# BusPirate-v5.net
KiCad netlist of a schematic drawn in EAGLE
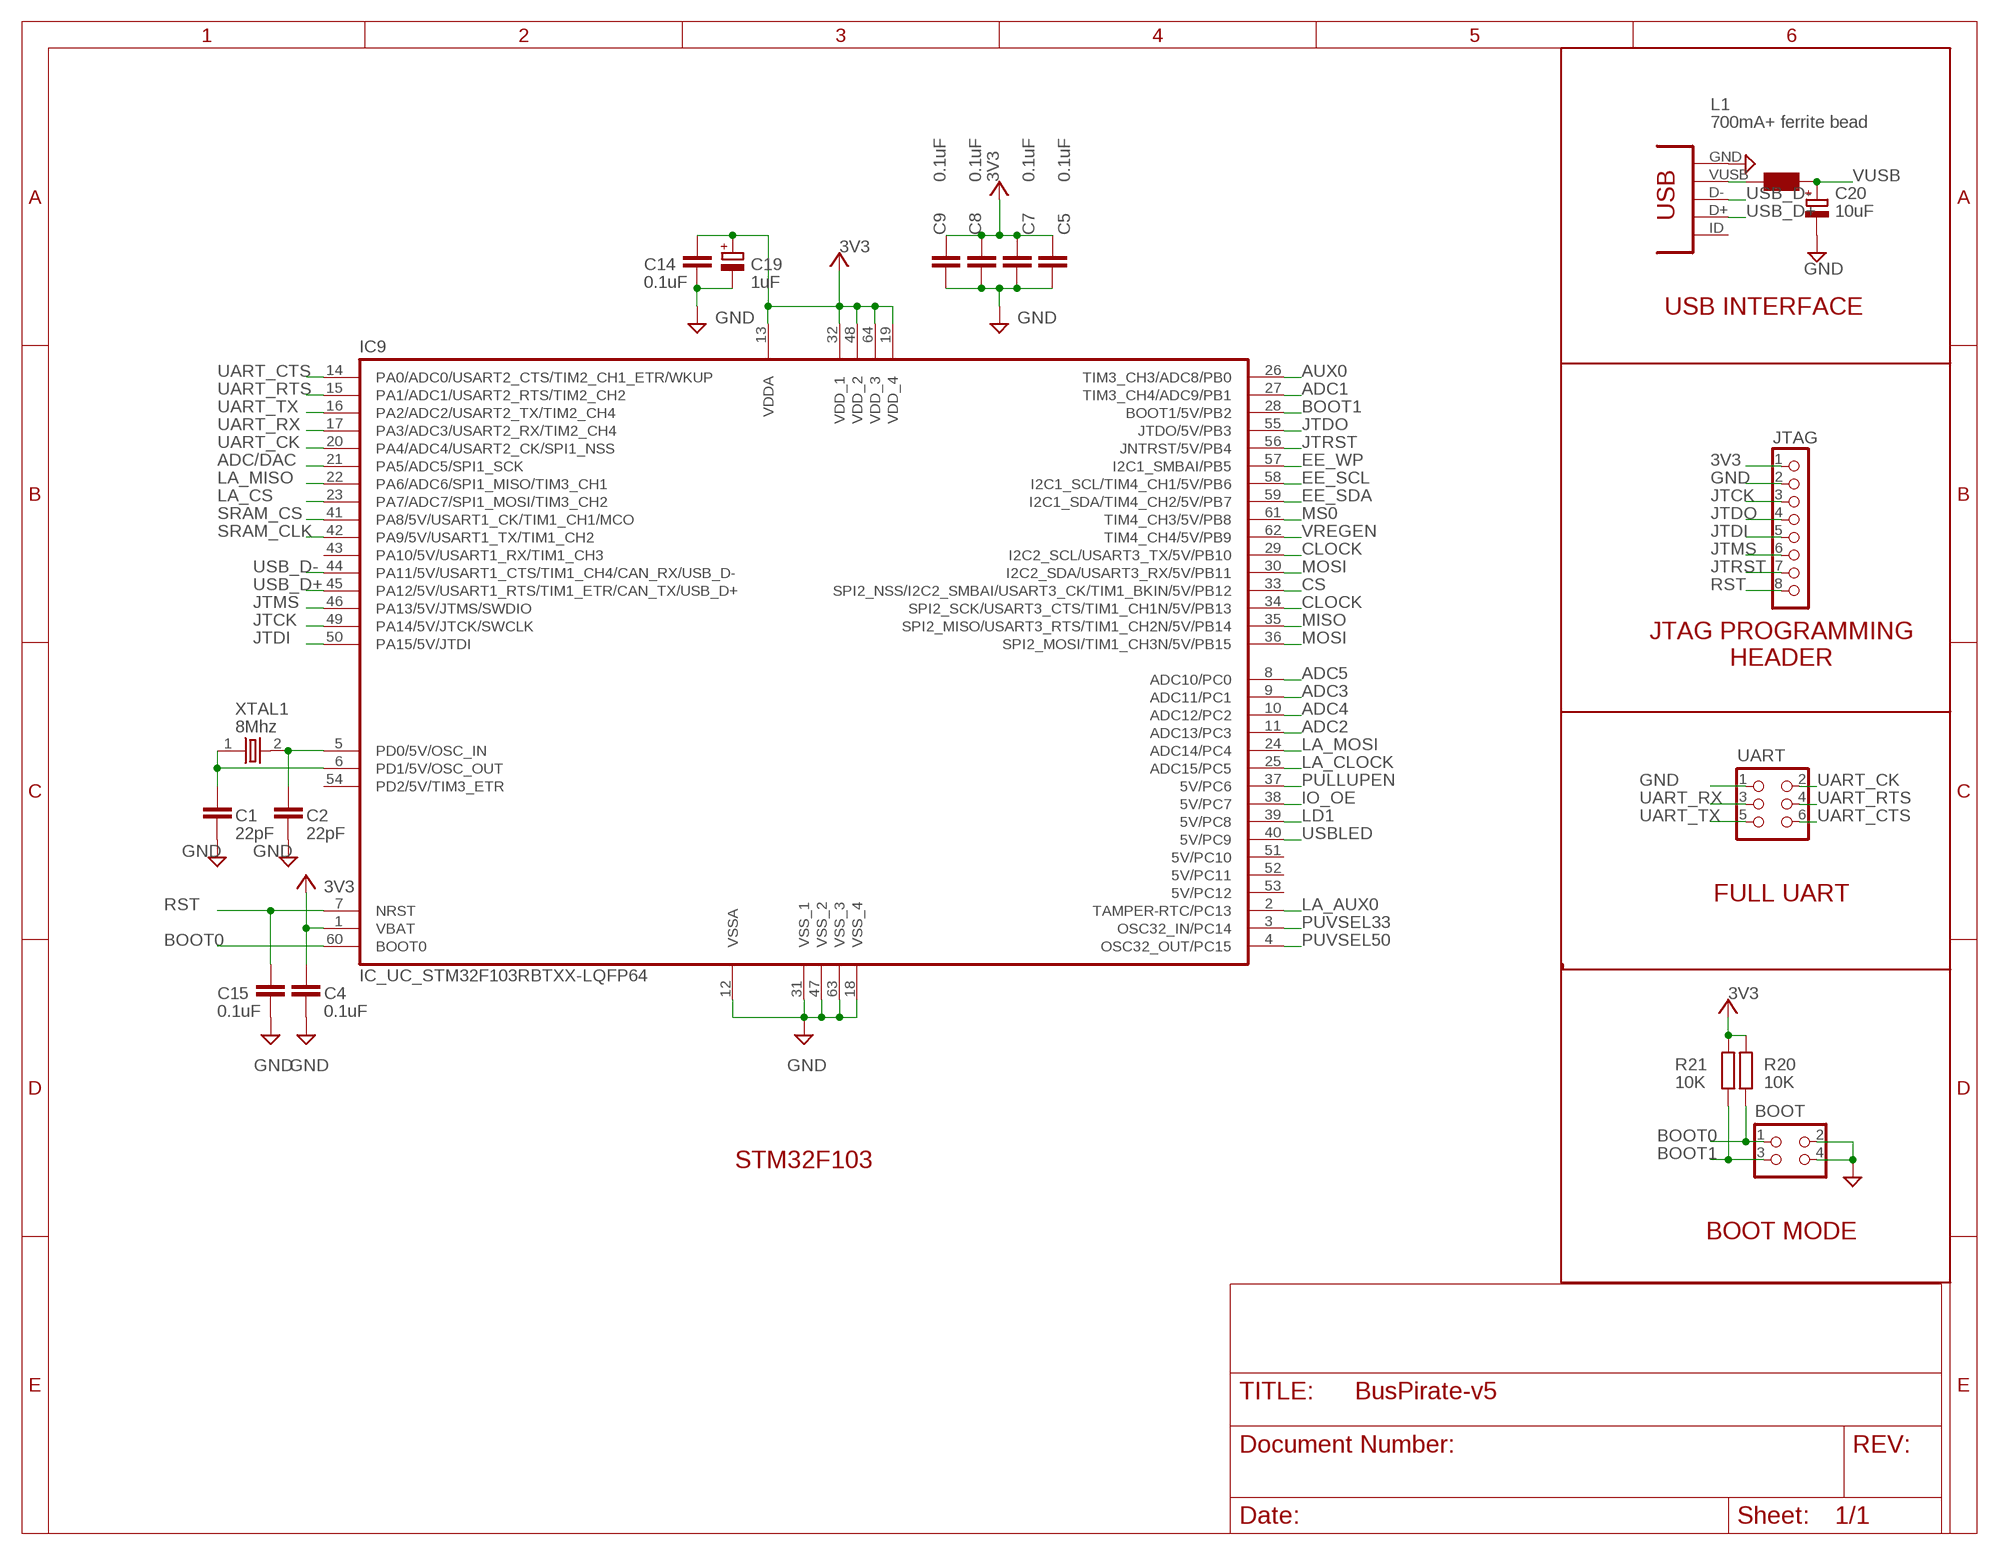
[diagram p0: schematic, sheet 1, part 1 of 2]
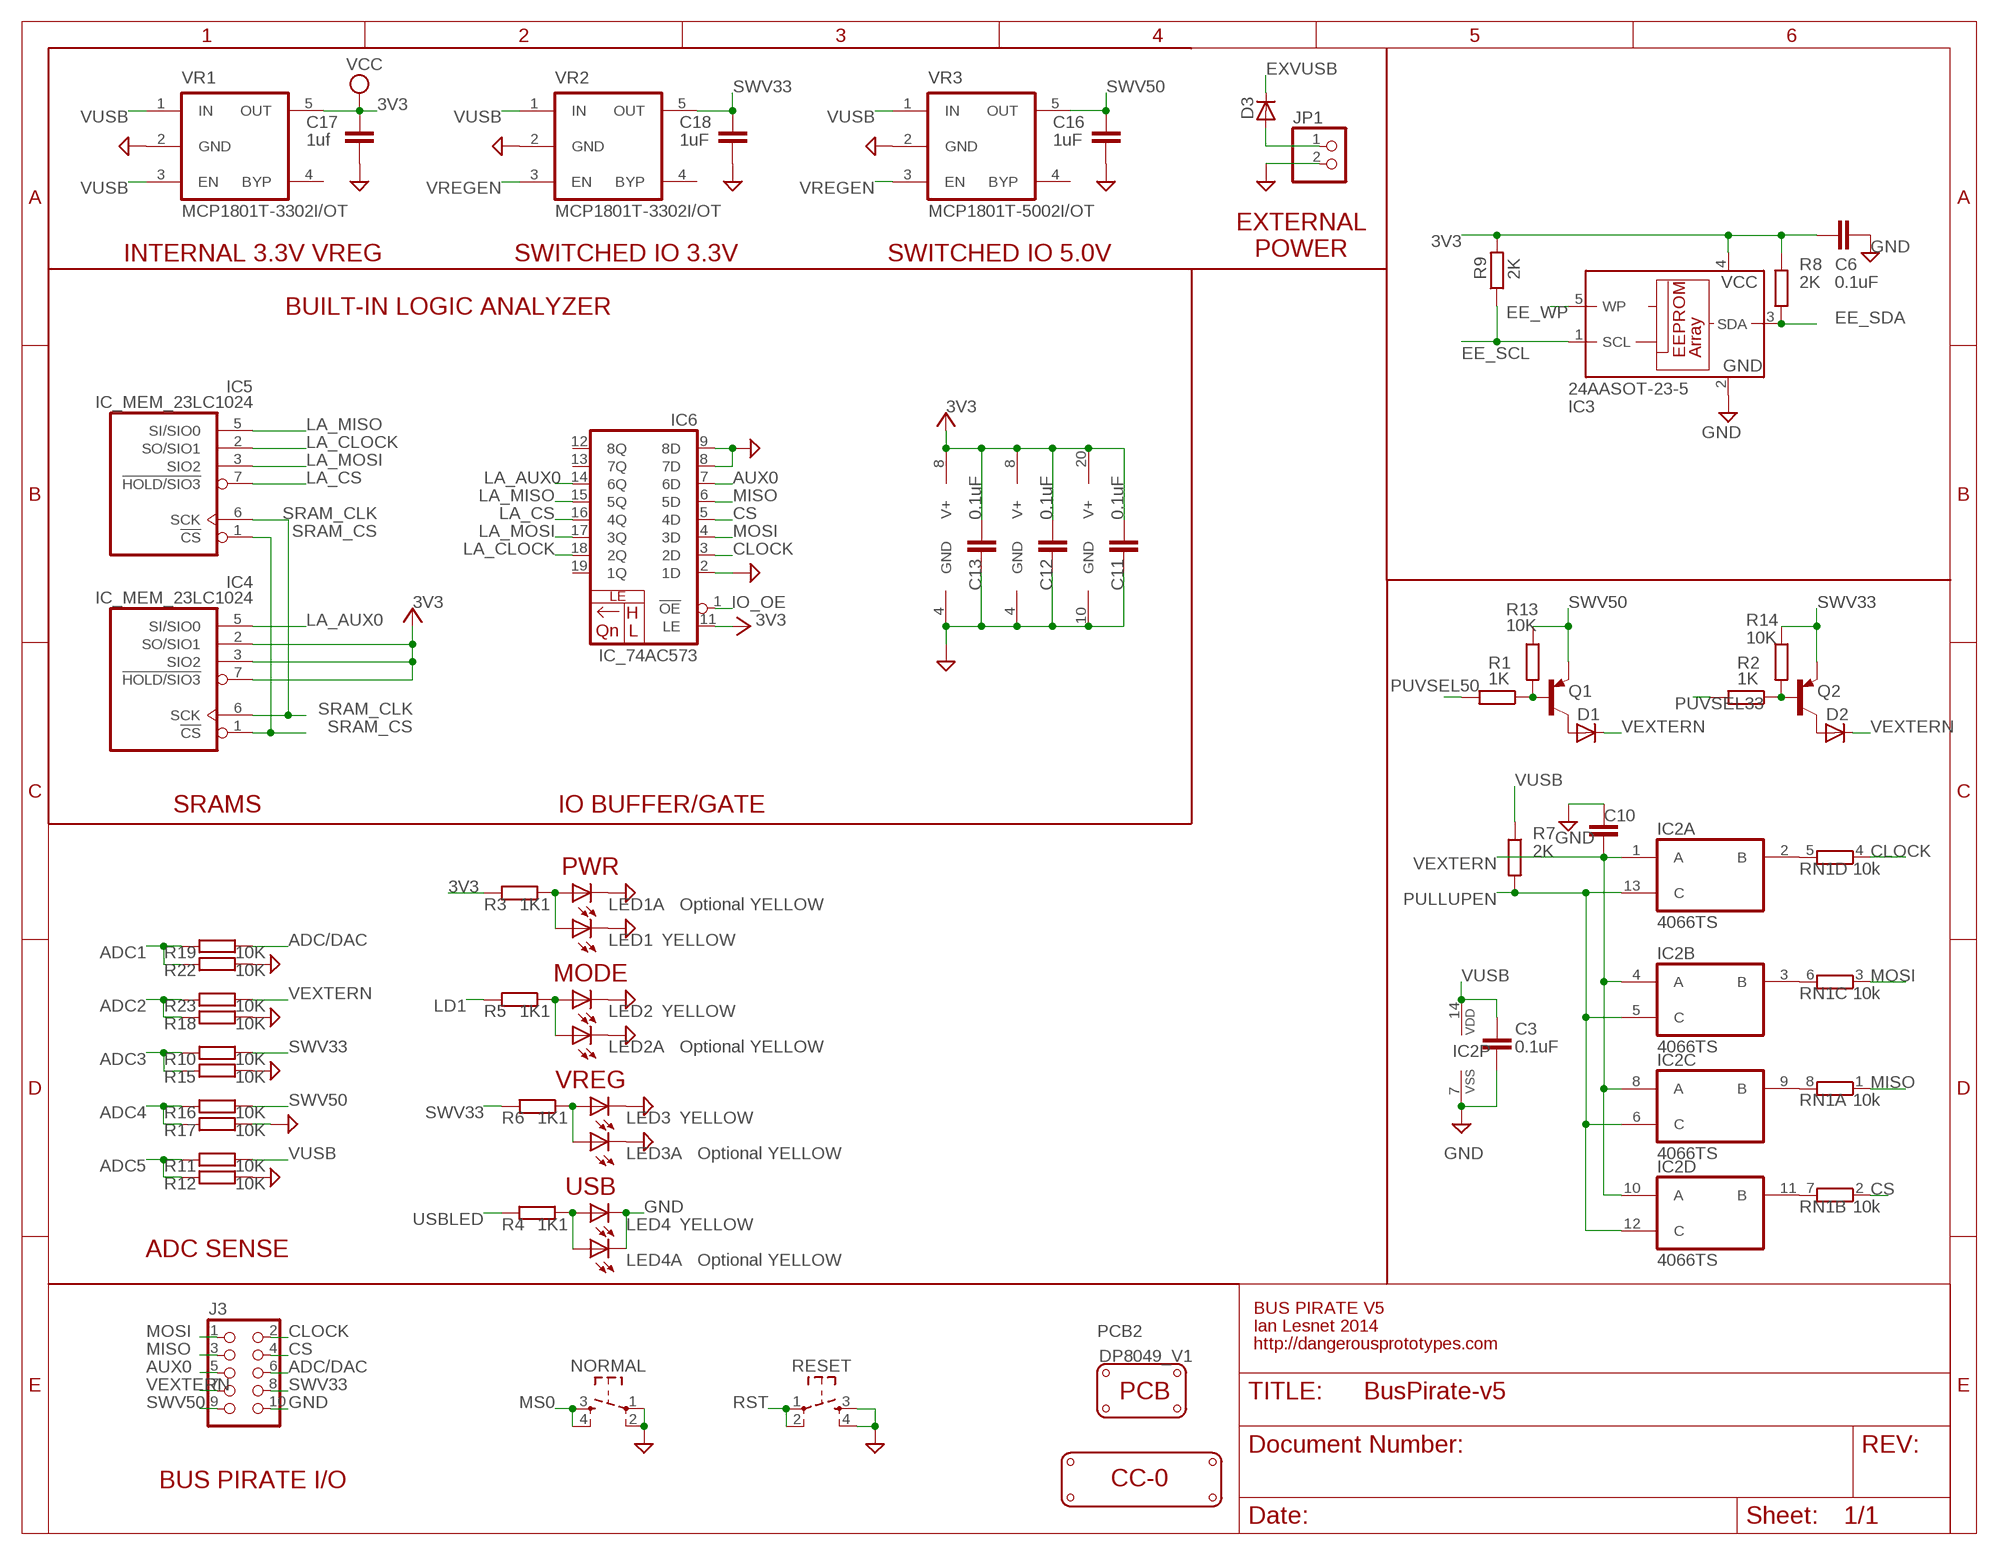
[diagram p1: schematic, sheet 1, part 2 of 2]

(export (version "E")
  (design (tool "Eeschema 10.0.6"))
  (components
    (comp (ref "BOOT")
      (value "CON_HEADER_2X02-PTH")
      (footprint "eagle-import:M2X2")
      (libsource (lib "eagle-import") (part "CON_HEADER_2X02-PTH"))
    )
    (comp (ref "C1")
      (value "22pF")
      (footprint "eagle-import:C0603")
      (libsource (lib "eagle-import") (part "C-EUC0603"))
    )
    (comp (ref "C2")
      (value "22pF")
      (footprint "eagle-import:C0603")
      (libsource (lib "eagle-import") (part "C-EUC0603"))
    )
    (comp (ref "C3")
      (value "0.1uF")
      (footprint "eagle-import:C0603")
      (libsource (lib "eagle-import") (part "C-EUC0603"))
    )
    (comp (ref "C4")
      (value "0.1uF")
      (footprint "eagle-import:C0603")
      (libsource (lib "eagle-import") (part "C-EUC0603"))
    )
    (comp (ref "C5")
      (value "0.1uF")
      (footprint "eagle-import:C0603")
      (libsource (lib "eagle-import") (part "C-EUC0603"))
    )
    (comp (ref "C6")
      (value "0.1uF")
      (footprint "eagle-import:C0603")
      (libsource (lib "eagle-import") (part "C-EUC0603"))
    )
    (comp (ref "C7")
      (value "0.1uF")
      (footprint "eagle-import:C0603")
      (libsource (lib "eagle-import") (part "C-EUC0603"))
    )
    (comp (ref "C8")
      (value "0.1uF")
      (footprint "eagle-import:C0603")
      (libsource (lib "eagle-import") (part "C-EUC0603"))
    )
    (comp (ref "C9")
      (value "0.1uF")
      (footprint "eagle-import:C0603")
      (libsource (lib "eagle-import") (part "C-EUC0603"))
    )
    (comp (ref "C10")
      (value "0.1uF")
      (footprint "eagle-import:C0603")
      (libsource (lib "eagle-import") (part "C-EUC0603"))
    )
    (comp (ref "C11")
      (value "0.1uF")
      (footprint "eagle-import:C0603")
      (libsource (lib "eagle-import") (part "C-EUC0603"))
    )
    (comp (ref "C12")
      (value "0.1uF")
      (footprint "eagle-import:C0603")
      (libsource (lib "eagle-import") (part "C-EUC0603"))
    )
    (comp (ref "C13")
      (value "0.1uF")
      (footprint "eagle-import:C0603")
      (libsource (lib "eagle-import") (part "C-EUC0603"))
    )
    (comp (ref "C14")
      (value "0.1uF")
      (footprint "eagle-import:C0603")
      (libsource (lib "eagle-import") (part "C-EUC0603"))
    )
    (comp (ref "C15")
      (value "0.1uF")
      (footprint "eagle-import:C0603")
      (libsource (lib "eagle-import") (part "C-EUC0603"))
    )
    (comp (ref "C16")
      (value "1uF")
      (footprint "eagle-import:C0603")
      (libsource (lib "eagle-import") (part "C-EUC0603"))
    )
    (comp (ref "C17")
      (value "1uf")
      (footprint "eagle-import:C0603")
      (libsource (lib "eagle-import") (part "C-EUC0603"))
    )
    (comp (ref "C18")
      (value "1uF")
      (footprint "eagle-import:C0603")
      (libsource (lib "eagle-import") (part "C-EUC0603"))
    )
    (comp (ref "C19")
      (value "1uF")
      (footprint "eagle-import:SMC_A")
      (libsource (lib "eagle-import") (part "CPOL-EUSMCA"))
    )
    (comp (ref "C20")
      (value "10uF")
      (footprint "eagle-import:SMC_A")
      (libsource (lib "eagle-import") (part "CPOL-EUSMCA"))
    )
    (comp (ref "D1")
      (value "MBR0520LT")
      (footprint "eagle-import:SOD123")
      (libsource (lib "eagle-import") (part "MBR0520LT"))
    )
    (comp (ref "D2")
      (value "MBR0520LT")
      (footprint "eagle-import:SOD123")
      (libsource (lib "eagle-import") (part "MBR0520LT"))
    )
    (comp (ref "D3")
      (value "MBR0520LT")
      (footprint "eagle-import:SOD123")
      (libsource (lib "eagle-import") (part "MBR0520LT"))
    )
    (comp (ref "IC2")
      (value "4066TS")
      (footprint "eagle-import:40XX_TSSOP14")
      (libsource (lib "eagle-import") (part "4066TS"))
    )
    (comp (ref "IC3")
      (value "24AASOT-23-5")
      (footprint "eagle-import:SOT-23-5@1")
      (libsource (lib "eagle-import") (part "24AA"))
    )
    (comp (ref "IC4")
      (value "IC_MEM_23LC1024")
      (footprint "eagle-import:SOIC-8")
      (libsource (lib "eagle-import") (part "IC_MEM_23LC1024"))
    )
    (comp (ref "IC5")
      (value "IC_MEM_23LC1024")
      (footprint "eagle-import:SOIC-8")
      (libsource (lib "eagle-import") (part "IC_MEM_23LC1024"))
    )
    (comp (ref "IC6")
      (value "IC_74AC573")
      (footprint "eagle-import:TSSOP-20")
      (libsource (lib "eagle-import") (part "IC_74AC573-TSSOP-20"))
    )
    (comp (ref "IC9")
      (value "IC_UC_STM32F103RBTXX-LQFP64")
      (footprint "eagle-import:LQFP64")
      (libsource (lib "eagle-import") (part "IC_UC_STM32F103RBTXX-LQFP64"))
    )
    (comp (ref "J3")
      (value "CON_HEADER_2X05-PTH+SHROUDED_A")
      (footprint "eagle-import:PINSHRD_PTH_2X05")
      (libsource (lib "eagle-import") (part "CON_HEADER_2X05-PTH+SHROUDED_A"))
    )
    (comp (ref "JP1")
      (value "PINHD-1X02_2.54-S")
      (footprint "eagle-import:1X02-S")
      (libsource (lib "eagle-import") (part "PINHD-1X02_2.54-S"))
    )
    (comp (ref "JTAG")
      (value "CON_HEADER_1X08-PTH")
      (footprint "eagle-import:M1X8")
      (libsource (lib "eagle-import") (part "CON_HEADER_1X08-PTH"))
    )
    (comp (ref "L1")
      (value "700mA+ ferrite bead")
      (footprint "eagle-import:WE-KI_0805_B")
      (libsource (lib "eagle-import") (part "WE-KIL_0805"))
    )
    (comp (ref "LED1")
      (value "YELLOW")
      (footprint "eagle-import:LED-603")
      (libsource (lib "eagle-import") (part "LED-0603"))
    )
    (comp (ref "LED1A")
      (value "Optional YELLOW")
      (footprint "eagle-import:LED-603")
      (libsource (lib "eagle-import") (part "LED-0603"))
    )
    (comp (ref "LED2")
      (value "YELLOW")
      (footprint "eagle-import:LED-603")
      (libsource (lib "eagle-import") (part "LED-0603"))
    )
    (comp (ref "LED2A")
      (value "Optional YELLOW")
      (footprint "eagle-import:LED-603")
      (libsource (lib "eagle-import") (part "LED-0603"))
    )
    (comp (ref "LED3")
      (value "YELLOW")
      (footprint "eagle-import:LED-603")
      (libsource (lib "eagle-import") (part "LED-0603"))
    )
    (comp (ref "LED3A")
      (value "Optional YELLOW")
      (footprint "eagle-import:LED-603")
      (libsource (lib "eagle-import") (part "LED-0603"))
    )
    (comp (ref "LED4")
      (value "YELLOW")
      (footprint "eagle-import:LED-603")
      (libsource (lib "eagle-import") (part "LED-0603"))
    )
    (comp (ref "LED4A")
      (value "Optional YELLOW")
      (footprint "eagle-import:LED-603")
      (libsource (lib "eagle-import") (part "LED-0603"))
    )
    (comp (ref "LOGO1")
      (value "LOGO_CC-0")
      (footprint "eagle-import:LOGO_CC-0")
      (libsource (lib "eagle-import") (part "LOGO_CC-0"))
    )
    (comp (ref "NORMAL")
      (value "SW_TACT_4P")
      (footprint "eagle-import:SW_TACT_SMALL")
      (libsource (lib "eagle-import") (part "SW_TACT_4P"))
    )
    (comp (ref "PCB2")
      (value "PCB_DP_RECTANGLE-80X49")
      (footprint "eagle-import:DP8049_V1")
      (fields (field (name "PCB_SIZE") "DP8049_V1"))
      (libsource (lib "eagle-import") (part "PCB_DP_RECTANGLE-80X49"))
    )
    (comp (ref "Q1")
      (value "MMBTA56-SOT23")
      (footprint "eagle-import:SOT23")
      (libsource (lib "eagle-import") (part "-?SOT23MMBTA56"))
    )
    (comp (ref "Q2")
      (value "MMBTA56-SOT23")
      (footprint "eagle-import:SOT23")
      (libsource (lib "eagle-import") (part "-?SOT23MMBTA56"))
    )
    (comp (ref "R1")
      (value "1K")
      (footprint "eagle-import:R0603")
      (libsource (lib "eagle-import") (part "R-EU_R0603"))
    )
    (comp (ref "R2")
      (value "1K")
      (footprint "eagle-import:R0603")
      (libsource (lib "eagle-import") (part "R-EU_R0603"))
    )
    (comp (ref "R3")
      (value "1K1")
      (footprint "eagle-import:R603")
      (libsource (lib "eagle-import") (part "RESISTOR-0603"))
    )
    (comp (ref "R4")
      (value "1K1")
      (footprint "eagle-import:R603")
      (libsource (lib "eagle-import") (part "RESISTOR-0603"))
    )
    (comp (ref "R5")
      (value "1K1")
      (footprint "eagle-import:R603")
      (libsource (lib "eagle-import") (part "RESISTOR-0603"))
    )
    (comp (ref "R6")
      (value "1K1")
      (footprint "eagle-import:R603")
      (libsource (lib "eagle-import") (part "RESISTOR-0603"))
    )
    (comp (ref "R7")
      (value "2K")
      (footprint "eagle-import:R0603")
      (libsource (lib "eagle-import") (part "R-EU_R0603"))
    )
    (comp (ref "R8")
      (value "2K")
      (footprint "eagle-import:R0603")
      (libsource (lib "eagle-import") (part "R-EU_R0603"))
    )
    (comp (ref "R9")
      (value "2K")
      (footprint "eagle-import:R0603")
      (libsource (lib "eagle-import") (part "R-EU_R0603"))
    )
    (comp (ref "R10")
      (value "10K")
      (footprint "eagle-import:R0603")
      (libsource (lib "eagle-import") (part "resistor_R-EU_R0603"))
    )
    (comp (ref "R11")
      (value "10K")
      (footprint "eagle-import:R0603")
      (libsource (lib "eagle-import") (part "resistor_R-EU_R0603"))
    )
    (comp (ref "R12")
      (value "10K")
      (footprint "eagle-import:R0603")
      (libsource (lib "eagle-import") (part "resistor_R-EU_R0603"))
    )
    (comp (ref "R13")
      (value "10K")
      (footprint "eagle-import:R603")
      (libsource (lib "eagle-import") (part "RESISTOR-0603"))
    )
    (comp (ref "R14")
      (value "10K")
      (footprint "eagle-import:R0603")
      (libsource (lib "eagle-import") (part "R-EU_R0603"))
    )
    (comp (ref "R15")
      (value "10K")
      (footprint "eagle-import:R0603")
      (libsource (lib "eagle-import") (part "resistor_R-EU_R0603"))
    )
    (comp (ref "R16")
      (value "10K")
      (footprint "eagle-import:R0603")
      (libsource (lib "eagle-import") (part "resistor_R-EU_R0603"))
    )
    (comp (ref "R17")
      (value "10K")
      (footprint "eagle-import:R0603")
      (libsource (lib "eagle-import") (part "resistor_R-EU_R0603"))
    )
    (comp (ref "R18")
      (value "10K")
      (footprint "eagle-import:R0603")
      (libsource (lib "eagle-import") (part "resistor_R-EU_R0603"))
    )
    (comp (ref "R19")
      (value "10K")
      (footprint "eagle-import:R0603")
      (libsource (lib "eagle-import") (part "resistor_R-EU_R0603"))
    )
    (comp (ref "R20")
      (value "10K")
      (footprint "eagle-import:R0603")
      (libsource (lib "eagle-import") (part "R-EU_R0603"))
    )
    (comp (ref "R21")
      (value "10K")
      (footprint "eagle-import:R0603")
      (libsource (lib "eagle-import") (part "R-EU_R0603"))
    )
    (comp (ref "R22")
      (value "10K")
      (footprint "eagle-import:R0603")
      (libsource (lib "eagle-import") (part "resistor_R-EU_R0603"))
    )
    (comp (ref "R23")
      (value "10K")
      (footprint "eagle-import:R0603")
      (libsource (lib "eagle-import") (part "resistor_R-EU_R0603"))
    )
    (comp (ref "RESET")
      (value "SW_TACT_4P")
      (footprint "eagle-import:SW_TACT_SMALL")
      (libsource (lib "eagle-import") (part "SW_TACT_4P"))
    )
    (comp (ref "RN1")
      (value "10k")
      (footprint "eagle-import:RN8P-4R-CRA06S")
      (libsource (lib "eagle-import") (part "RNETWORK"))
    )
    (comp (ref "UART")
      (value "CON_HEADER_2X03-PTH")
      (footprint "eagle-import:M2X3")
      (libsource (lib "eagle-import") (part "CON_HEADER_2X03-PTH"))
    )
    (comp (ref "USB")
      (value "USB mini-b")
      (footprint "eagle-import:CONN_USB_MINI-B")
      (libsource (lib "eagle-import") (part "CON-USB-MINI-BUSB1"))
    )
    (comp (ref "VR1")
      (value "MCP1801T-3302I/OT")
      (footprint "eagle-import:SOT-23-5@1")
      (libsource (lib "eagle-import") (part "MIC5205"))
    )
    (comp (ref "VR2")
      (value "MCP1801T-3302I/OT")
      (footprint "eagle-import:SOT-23-5@1")
      (libsource (lib "eagle-import") (part "MIC5205"))
    )
    (comp (ref "VR3")
      (value "MCP1801T-5002I/OT")
      (footprint "eagle-import:SOT-23-5@1")
      (libsource (lib "eagle-import") (part "MIC5205"))
    )
    (comp (ref "XTAL1")
      (value "8Mhz")
      (footprint "eagle-import:XTAL_4X6")
      (libsource (lib "eagle-import") (part "OSC-XTAL-12M"))
    )
  )
  (nets
    (net (code "1") (name "/ADC1") (class "Default")
      (node (ref "IC9") (pin "27") (pinfunction "TIM3_CH4/ADC9/PB1_27") (pintype "bidirectional"))
      (node (ref "R19") (pin "2") (pinfunction "2_2") (pintype "passive"))
      (node (ref "R22") (pin "2") (pinfunction "2_2") (pintype "passive"))
    )
    (net (code "2") (name "/ADC2") (class "Default")
      (node (ref "IC9") (pin "11") (pinfunction "ADC13/PC3_11") (pintype "bidirectional"))
      (node (ref "R18") (pin "2") (pinfunction "2_2") (pintype "passive"))
      (node (ref "R23") (pin "2") (pinfunction "2_2") (pintype "passive"))
    )
    (net (code "3") (name "/ADC3") (class "Default")
      (node (ref "IC9") (pin "9") (pinfunction "ADC11/PC1_9") (pintype "bidirectional"))
      (node (ref "R10") (pin "2") (pinfunction "2_2") (pintype "passive"))
      (node (ref "R15") (pin "2") (pinfunction "2_2") (pintype "passive"))
    )
    (net (code "4") (name "/ADC4") (class "Default")
      (node (ref "IC9") (pin "10") (pinfunction "ADC12/PC2_10") (pintype "bidirectional"))
      (node (ref "R16") (pin "2") (pinfunction "2_2") (pintype "passive"))
      (node (ref "R17") (pin "2") (pinfunction "2_2") (pintype "passive"))
    )
    (net (code "5") (name "/ADC5") (class "Default")
      (node (ref "IC9") (pin "8") (pinfunction "ADC10/PC0_8") (pintype "bidirectional"))
      (node (ref "R11") (pin "2") (pinfunction "2_2") (pintype "passive"))
      (node (ref "R12") (pin "2") (pinfunction "2_2") (pintype "passive"))
    )
    (net (code "6") (name "/ADC{slash}DAC") (class "Default")
      (node (ref "IC9") (pin "21") (pinfunction "PA5/ADC5/SPI1_SCK_21") (pintype "bidirectional"))
      (node (ref "J3") (pin "6") (pinfunction "6_6") (pintype "passive"))
      (node (ref "R19") (pin "1") (pinfunction "1_1") (pintype "passive"))
    )
    (net (code "7") (name "/AUX0") (class "Default")
      (node (ref "IC6") (pin "7") (pinfunction "6D_7") (pintype "bidirectional"))
      (node (ref "IC9") (pin "26") (pinfunction "TIM3_CH3/ADC8/PB0_26") (pintype "bidirectional"))
      (node (ref "J3") (pin "5") (pinfunction "5_5") (pintype "passive"))
    )
    (net (code "8") (name "/BOOT0") (class "Default")
      (node (ref "BOOT") (pin "1") (pinfunction "1_1") (pintype "passive"))
      (node (ref "IC9") (pin "60") (pinfunction "BOOT0_60") (pintype "input"))
      (node (ref "R20") (pin "1") (pinfunction "1_1") (pintype "passive"))
    )
    (net (code "9") (name "/BOOT1") (class "Default")
      (node (ref "BOOT") (pin "3") (pinfunction "3_3") (pintype "passive"))
      (node (ref "IC9") (pin "28") (pinfunction "BOOT1/5V/PB2_28") (pintype "bidirectional"))
      (node (ref "R21") (pin "1") (pinfunction "1_1") (pintype "passive"))
    )
    (net (code "10") (name "/CLOCK") (class "Default")
      (node (ref "IC6") (pin "3") (pinfunction "2D_3") (pintype "bidirectional"))
      (node (ref "IC9") (pin "29") (pinfunction "I2C2_SCL/USART3_TX/5V/PB10_29") (pintype "bidirectional"))
      (node (ref "IC9") (pin "34") (pinfunction "SPI2_SCK/USART3_CTS/TIM1_CH1N/5V/PB13_34") (pintype "bidirectional"))
      (node (ref "J3") (pin "2") (pinfunction "2_2") (pintype "passive"))
      (node (ref "RN1") (pin "4") (pinfunction "1_4") (pintype "passive"))
    )
    (net (code "11") (name "/CS") (class "Default")
      (node (ref "IC6") (pin "5") (pinfunction "4D_5") (pintype "bidirectional"))
      (node (ref "IC9") (pin "33") (pinfunction "SPI2_NSS/I2C2_SMBAI/USART3_CK/TIM1_BKIN/5V/PB12_33") (pintype "bidirectional"))
      (node (ref "J3") (pin "4") (pinfunction "4_4") (pintype "passive"))
      (node (ref "RN1") (pin "2") (pinfunction "1_2") (pintype "passive"))
    )
    (net (code "12") (name "/EE_SCL") (class "Default")
      (node (ref "IC3") (pin "1") (pinfunction "SCL_1") (pintype "input"))
      (node (ref "IC9") (pin "58") (pinfunction "I2C1_SCL/TIM4_CH1/5V/PB6_58") (pintype "bidirectional"))
      (node (ref "R9") (pin "1") (pinfunction "1_1") (pintype "passive"))
    )
    (net (code "13") (name "/EE_SDA") (class "Default")
      (node (ref "IC3") (pin "3") (pinfunction "SDA_3") (pintype "bidirectional"))
      (node (ref "IC9") (pin "59") (pinfunction "I2C1_SDA/TIM4_CH2/5V/PB7_59") (pintype "bidirectional"))
      (node (ref "R8") (pin "1") (pinfunction "1_1") (pintype "passive"))
    )
    (net (code "14") (name "/EE_WP") (class "Default")
      (node (ref "IC3") (pin "5") (pinfunction "WP_5") (pintype "input"))
      (node (ref "IC9") (pin "57") (pinfunction "I2C1_SMBAI/PB5_57") (pintype "bidirectional"))
    )
    (net (code "15") (name "/EXVUSB") (class "Default")
      (node (ref "D3") (pin "C") (pinfunction "C_C") (pintype "passive"))
      (node (ref "L1") (pin "2") (pinfunction "1_2") (pintype "passive"))
      (node (ref "USB") (pin "VUSB") (pinfunction "VUSB_VUSB") (pintype "bidirectional"))
    )
    (net (code "16") (name "/IO_OE") (class "Default")
      (node (ref "IC6") (pin "1") (pinfunction "~{OE}_1") (pintype "input"))
      (node (ref "IC9") (pin "38") (pinfunction "5V/PC7_38") (pintype "bidirectional"))
    )
    (net (code "17") (name "/JTCK") (class "Default")
      (node (ref "IC9") (pin "49") (pinfunction "PA14/5V/JTCK/SWCLK_49") (pintype "bidirectional"))
      (node (ref "JTAG") (pin "3") (pinfunction "3_3") (pintype "passive"))
    )
    (net (code "18") (name "/JTDI") (class "Default")
      (node (ref "IC9") (pin "50") (pinfunction "PA15/5V/JTDI_50") (pintype "bidirectional"))
      (node (ref "JTAG") (pin "5") (pinfunction "5_5") (pintype "passive"))
    )
    (net (code "19") (name "/JTDO") (class "Default")
      (node (ref "IC9") (pin "55") (pinfunction "JTDO/5V/PB3_55") (pintype "bidirectional"))
      (node (ref "JTAG") (pin "4") (pinfunction "4_4") (pintype "passive"))
    )
    (net (code "20") (name "/JTMS") (class "Default")
      (node (ref "IC9") (pin "46") (pinfunction "PA13/5V/JTMS/SWDIO_46") (pintype "bidirectional"))
      (node (ref "JTAG") (pin "6") (pinfunction "6_6") (pintype "passive"))
    )
    (net (code "21") (name "/JTRST") (class "Default")
      (node (ref "IC9") (pin "56") (pinfunction "JNTRST/5V/PB4_56") (pintype "bidirectional"))
      (node (ref "JTAG") (pin "7") (pinfunction "7_7") (pintype "passive"))
    )
    (net (code "22") (name "/LA_AUX0") (class "Default")
      (node (ref "IC4") (pin "5") (pinfunction "SI/SIO0_5") (pintype "bidirectional"))
      (node (ref "IC6") (pin "14") (pinfunction "6Q_14") (pintype "bidirectional"))
      (node (ref "IC9") (pin "2") (pinfunction "TAMPER-RTC/PC13_2") (pintype "bidirectional"))
    )
    (net (code "23") (name "/LA_CLOCK") (class "Default")
      (node (ref "IC5") (pin "2") (pinfunction "SO/SIO1_2") (pintype "bidirectional"))
      (node (ref "IC6") (pin "18") (pinfunction "2Q_18") (pintype "bidirectional"))
      (node (ref "IC9") (pin "25") (pinfunction "ADC15/PC5_25") (pintype "bidirectional"))
    )
    (net (code "24") (name "/LA_CS") (class "Default")
      (node (ref "IC5") (pin "7") (pinfunction "~{HOLD/SIO3}_7") (pintype "input"))
      (node (ref "IC6") (pin "16") (pinfunction "4Q_16") (pintype "bidirectional"))
      (node (ref "IC9") (pin "23") (pinfunction "PA7/ADC7/SPI1_MOSI/TIM3_CH2_23") (pintype "bidirectional"))
    )
    (net (code "25") (name "/LA_MISO") (class "Default")
      (node (ref "IC5") (pin "5") (pinfunction "SI/SIO0_5") (pintype "bidirectional"))
      (node (ref "IC6") (pin "15") (pinfunction "5Q_15") (pintype "bidirectional"))
      (node (ref "IC9") (pin "22") (pinfunction "PA6/ADC6/SPI1_MISO/TIM3_CH1_22") (pintype "bidirectional"))
    )
    (net (code "26") (name "/LA_MOSI") (class "Default")
      (node (ref "IC5") (pin "3") (pinfunction "SIO2_3") (pintype "bidirectional"))
      (node (ref "IC6") (pin "17") (pinfunction "3Q_17") (pintype "bidirectional"))
      (node (ref "IC9") (pin "24") (pinfunction "ADC14/PC4_24") (pintype "bidirectional"))
    )
    (net (code "27") (name "/LD1") (class "Default")
      (node (ref "IC9") (pin "39") (pinfunction "5V/PC8_39") (pintype "bidirectional"))
      (node (ref "R5") (pin "2") (pinfunction "2_2") (pintype "passive"))
    )
    (net (code "28") (name "/MISO") (class "Default")
      (node (ref "IC6") (pin "6") (pinfunction "5D_6") (pintype "bidirectional"))
      (node (ref "IC9") (pin "35") (pinfunction "SPI2_MISO/USART3_RTS/TIM1_CH2N/5V/PB14_35") (pintype "bidirectional"))
      (node (ref "J3") (pin "3") (pinfunction "3_3") (pintype "passive"))
      (node (ref "RN1") (pin "1") (pinfunction "1_1") (pintype "passive"))
    )
    (net (code "29") (name "/MOSI") (class "Default")
      (node (ref "IC6") (pin "4") (pinfunction "3D_4") (pintype "bidirectional"))
      (node (ref "IC9") (pin "30") (pinfunction "I2C2_SDA/USART3_RX/5V/PB11_30") (pintype "bidirectional"))
      (node (ref "IC9") (pin "36") (pinfunction "SPI2_MOSI/TIM1_CH3N/5V/PB15_36") (pintype "bidirectional"))
      (node (ref "J3") (pin "1") (pinfunction "1_1") (pintype "passive"))
      (node (ref "RN1") (pin "3") (pinfunction "1_3") (pintype "passive"))
    )
    (net (code "30") (name "/MS0") (class "Default")
      (node (ref "IC9") (pin "61") (pinfunction "TIM4_CH3/5V/PB8_61") (pintype "bidirectional"))
      (node (ref "NORMAL") (pin "3") (pinfunction "3_3") (pintype "passive"))
      (node (ref "NORMAL") (pin "4") (pinfunction "4_4") (pintype "passive"))
    )
    (net (code "31") (name "/PULLUPEN") (class "Default")
      (node (ref "IC2") (pin "12") (pinfunction "C_12") (pintype "input"))
      (node (ref "IC2") (pin "13") (pinfunction "C_13") (pintype "input"))
      (node (ref "IC2") (pin "5") (pinfunction "C_5") (pintype "input"))
      (node (ref "IC2") (pin "6") (pinfunction "C_6") (pintype "input"))
      (node (ref "IC9") (pin "37") (pinfunction "5V/PC6_37") (pintype "bidirectional"))
      (node (ref "R7") (pin "2") (pinfunction "2_2") (pintype "passive"))
    )
    (net (code "32") (name "/PUVSEL33") (class "Default")
      (node (ref "IC9") (pin "3") (pinfunction "OSC32_IN/PC14_3") (pintype "bidirectional"))
      (node (ref "R2") (pin "2") (pinfunction "2_2") (pintype "passive"))
    )
    (net (code "33") (name "/PUVSEL50") (class "Default")
      (node (ref "IC9") (pin "4") (pinfunction "OSC32_OUT/PC15_4") (pintype "bidirectional"))
      (node (ref "R1") (pin "2") (pinfunction "2_2") (pintype "passive"))
    )
    (net (code "34") (name "/RST") (class "Default")
      (node (ref "C15") (pin "2") (pinfunction "2_2") (pintype "passive"))
      (node (ref "IC9") (pin "7") (pinfunction "NRST_7") (pintype "bidirectional"))
      (node (ref "JTAG") (pin "8") (pinfunction "8_8") (pintype "passive"))
      (node (ref "RESET") (pin "1") (pinfunction "1_1") (pintype "passive"))
      (node (ref "RESET") (pin "2") (pinfunction "2_2") (pintype "passive"))
    )
    (net (code "35") (name "/SRAM_CLK") (class "Default")
      (node (ref "IC4") (pin "6") (pinfunction "SCK_6") (pintype "input"))
      (node (ref "IC5") (pin "6") (pinfunction "SCK_6") (pintype "input"))
      (node (ref "IC9") (pin "42") (pinfunction "PA9/5V/USART1_TX/TIM1_CH2_42") (pintype "bidirectional"))
    )
    (net (code "36") (name "/SRAM_CS") (class "Default")
      (node (ref "IC4") (pin "1") (pinfunction "~{CS}_1") (pintype "input"))
      (node (ref "IC5") (pin "1") (pinfunction "~{CS}_1") (pintype "input"))
      (node (ref "IC9") (pin "41") (pinfunction "PA8/5V/USART1_CK/TIM1_CH1/MCO_41") (pintype "bidirectional"))
    )
    (net (code "37") (name "/SWV33") (class "Default")
      (node (ref "C18") (pin "1") (pinfunction "1_1") (pintype "passive"))
      (node (ref "J3") (pin "8") (pinfunction "8_8") (pintype "passive"))
      (node (ref "Q2") (pin "2") (pinfunction "E_2") (pintype "passive"))
      (node (ref "R10") (pin "1") (pinfunction "1_1") (pintype "passive"))
      (node (ref "R14") (pin "1") (pinfunction "1_1") (pintype "passive"))
      (node (ref "R6") (pin "2") (pinfunction "2_2") (pintype "passive"))
      (node (ref "VR2") (pin "5") (pinfunction "OUT_5") (pintype "bidirectional"))
    )
    (net (code "38") (name "/SWV50") (class "Default")
      (node (ref "C16") (pin "1") (pinfunction "1_1") (pintype "passive"))
      (node (ref "J3") (pin "9") (pinfunction "9_9") (pintype "passive"))
      (node (ref "Q1") (pin "2") (pinfunction "E_2") (pintype "passive"))
      (node (ref "R13") (pin "1") (pinfunction "1_1") (pintype "passive"))
      (node (ref "R16") (pin "1") (pinfunction "1_1") (pintype "passive"))
      (node (ref "VR3") (pin "5") (pinfunction "OUT_5") (pintype "bidirectional"))
    )
    (net (code "39") (name "/UART_CK") (class "Default")
      (node (ref "IC9") (pin "20") (pinfunction "PA4/ADC4/USART2_CK/SPI1_NSS_20") (pintype "bidirectional"))
      (node (ref "UART") (pin "2") (pinfunction "2_2") (pintype "passive"))
    )
    (net (code "40") (name "/UART_CTS") (class "Default")
      (node (ref "IC9") (pin "14") (pinfunction "PA0/ADC0/USART2_CTS/TIM2_CH1_ETR/WKUP_14") (pintype "bidirectional"))
      (node (ref "UART") (pin "6") (pinfunction "6_6") (pintype "passive"))
    )
    (net (code "41") (name "/UART_RTS") (class "Default")
      (node (ref "IC9") (pin "15") (pinfunction "PA1/ADC1/USART2_RTS/TIM2_CH2_15") (pintype "bidirectional"))
      (node (ref "UART") (pin "4") (pinfunction "4_4") (pintype "passive"))
    )
    (net (code "42") (name "/UART_RX") (class "Default")
      (node (ref "IC9") (pin "17") (pinfunction "PA3/ADC3/USART2_RX/TIM2_CH4_17") (pintype "bidirectional"))
      (node (ref "UART") (pin "3") (pinfunction "3_3") (pintype "passive"))
    )
    (net (code "43") (name "/UART_TX") (class "Default")
      (node (ref "IC9") (pin "16") (pinfunction "PA2/ADC2/USART2_TX/TIM2_CH4_16") (pintype "bidirectional"))
      (node (ref "UART") (pin "5") (pinfunction "5_5") (pintype "passive"))
    )
    (net (code "44") (name "/USBLED") (class "Default")
      (node (ref "IC9") (pin "40") (pinfunction "5V/PC9_40") (pintype "bidirectional"))
      (node (ref "R4") (pin "2") (pinfunction "2_2") (pintype "passive"))
    )
    (net (code "45") (name "/USB_D+") (class "Default")
      (node (ref "IC9") (pin "45") (pinfunction "PA12/5V/USART1_RTS/TIM1_ETR/CAN_TX/USB_D+_45") (pintype "bidirectional"))
      (node (ref "USB") (pin "D+") (pinfunction "D+_D+") (pintype "bidirectional"))
    )
    (net (code "46") (name "/USB_D-") (class "Default")
      (node (ref "IC9") (pin "44") (pinfunction "PA11/5V/USART1_CTS/TIM1_CH4/CAN_RX/USB_D-_44") (pintype "bidirectional"))
      (node (ref "USB") (pin "D-") (pinfunction "D-_D-") (pintype "bidirectional"))
    )
    (net (code "47") (name "/VEXTERN") (class "Default")
      (node (ref "C10") (pin "1") (pinfunction "1_1") (pintype "passive"))
      (node (ref "D1") (pin "C") (pinfunction "C_C") (pintype "passive"))
      (node (ref "D2") (pin "C") (pinfunction "C_C") (pintype "passive"))
      (node (ref "IC2") (pin "1") (pinfunction "A_1") (pintype "tri_state"))
      (node (ref "IC2") (pin "10") (pinfunction "A_10") (pintype "tri_state"))
      (node (ref "IC2") (pin "4") (pinfunction "A_4") (pintype "tri_state"))
      (node (ref "IC2") (pin "8") (pinfunction "A_8") (pintype "tri_state"))
      (node (ref "J3") (pin "7") (pinfunction "7_7") (pintype "passive"))
      (node (ref "R23") (pin "1") (pinfunction "1_1") (pintype "passive"))
    )
    (net (code "48") (name "/VREGEN") (class "Default")
      (node (ref "IC9") (pin "62") (pinfunction "TIM4_CH4/5V/PB9_62") (pintype "bidirectional"))
      (node (ref "VR2") (pin "3") (pinfunction "EN_3") (pintype "bidirectional"))
      (node (ref "VR3") (pin "3") (pinfunction "EN_3") (pintype "bidirectional"))
    )
    (net (code "49") (name "/VUSB") (class "Default")
      (node (ref "C20") (pin "+") (pinfunction "+_+") (pintype "passive"))
      (node (ref "C3") (pin "1") (pinfunction "1_1") (pintype "passive"))
      (node (ref "IC2") (pin "14") (pinfunction "VDD_14") (pintype "power_in"))
      (node (ref "L1") (pin "1") (pinfunction "2_1") (pintype "passive"))
      (node (ref "R11") (pin "1") (pinfunction "1_1") (pintype "passive"))
      (node (ref "R7") (pin "1") (pinfunction "1_1") (pintype "passive"))
      (node (ref "VR1") (pin "1") (pinfunction "IN_1") (pintype "bidirectional"))
      (node (ref "VR1") (pin "3") (pinfunction "EN_3") (pintype "bidirectional"))
      (node (ref "VR2") (pin "1") (pinfunction "IN_1") (pintype "bidirectional"))
      (node (ref "VR3") (pin "1") (pinfunction "IN_1") (pintype "bidirectional"))
    )
    (net (code "50") (name "GND") (class "Default")
      (node (ref "BOOT") (pin "2") (pinfunction "2_2") (pintype "passive"))
      (node (ref "BOOT") (pin "4") (pinfunction "4_4") (pintype "passive"))
      (node (ref "C1") (pin "1") (pinfunction "1_1") (pintype "passive"))
      (node (ref "C10") (pin "2") (pinfunction "2_2") (pintype "passive"))
      (node (ref "C11") (pin "2") (pinfunction "2_2") (pintype "passive"))
      (node (ref "C12") (pin "2") (pinfunction "2_2") (pintype "passive"))
      (node (ref "C13") (pin "2") (pinfunction "2_2") (pintype "passive"))
      (node (ref "C14") (pin "1") (pinfunction "1_1") (pintype "passive"))
      (node (ref "C15") (pin "1") (pinfunction "1_1") (pintype "passive"))
      (node (ref "C16") (pin "2") (pinfunction "2_2") (pintype "passive"))
      (node (ref "C17") (pin "2") (pinfunction "2_2") (pintype "passive"))
      (node (ref "C18") (pin "2") (pinfunction "2_2") (pintype "passive"))
      (node (ref "C19") (pin "-") (pinfunction "-_-") (pintype "passive"))
      (node (ref "C2") (pin "1") (pinfunction "1_1") (pintype "passive"))
      (node (ref "C20") (pin "-") (pinfunction "-_-") (pintype "passive"))
      (node (ref "C3") (pin "2") (pinfunction "2_2") (pintype "passive"))
      (node (ref "C4") (pin "1") (pinfunction "1_1") (pintype "passive"))
      (node (ref "C5") (pin "1") (pinfunction "1_1") (pintype "passive"))
      (node (ref "C6") (pin "2") (pinfunction "2_2") (pintype "passive"))
      (node (ref "C7") (pin "1") (pinfunction "1_1") (pintype "passive"))
      (node (ref "C8") (pin "1") (pinfunction "1_1") (pintype "passive"))
      (node (ref "C9") (pin "1") (pinfunction "1_1") (pintype "passive"))
      (node (ref "IC2") (pin "7") (pinfunction "VSS_7") (pintype "power_in"))
      (node (ref "IC3") (pin "2") (pinfunction "GND_2") (pintype "power_in"))
      (node (ref "IC4") (pin "4") (pinfunction "GND_4") (pintype "power_in"))
      (node (ref "IC5") (pin "4") (pinfunction "GND_4") (pintype "power_in"))
      (node (ref "IC6") (pin "10") (pinfunction "GND_10") (pintype "power_in"))
      (node (ref "IC6") (pin "2") (pinfunction "1D_2") (pintype "bidirectional"))
      (node (ref "IC6") (pin "8") (pinfunction "7D_8") (pintype "bidirectional"))
      (node (ref "IC6") (pin "9") (pinfunction "8D_9") (pintype "bidirectional"))
      (node (ref "IC9") (pin "12") (pinfunction "VSSA_12") (pintype "power_in"))
      (node (ref "IC9") (pin "18") (pinfunction "VSS_4_18") (pintype "power_in"))
      (node (ref "IC9") (pin "31") (pinfunction "VSS_1_31") (pintype "power_in"))
      (node (ref "IC9") (pin "47") (pinfunction "VSS_2_47") (pintype "power_in"))
      (node (ref "IC9") (pin "63") (pinfunction "VSS_3_63") (pintype "power_in"))
      (node (ref "J3") (pin "10") (pinfunction "10_10") (pintype "passive"))
      (node (ref "JP1") (pin "2") (pinfunction "2_2") (pintype "passive"))
      (node (ref "JTAG") (pin "2") (pinfunction "2_2") (pintype "passive"))
      (node (ref "LED1") (pin "C") (pinfunction "C_C") (pintype "passive"))
      (node (ref "LED1A") (pin "C") (pinfunction "C_C") (pintype "passive"))
      (node (ref "LED2") (pin "C") (pinfunction "C_C") (pintype "passive"))
      (node (ref "LED2A") (pin "C") (pinfunction "C_C") (pintype "passive"))
      (node (ref "LED3") (pin "C") (pinfunction "C_C") (pintype "passive"))
      (node (ref "LED3A") (pin "C") (pinfunction "C_C") (pintype "passive"))
      (node (ref "LED4") (pin "C") (pinfunction "C_C") (pintype "passive"))
      (node (ref "LED4A") (pin "C") (pinfunction "C_C") (pintype "passive"))
      (node (ref "NORMAL") (pin "1") (pinfunction "1_1") (pintype "passive"))
      (node (ref "NORMAL") (pin "2") (pinfunction "2_2") (pintype "passive"))
      (node (ref "R12") (pin "1") (pinfunction "1_1") (pintype "passive"))
      (node (ref "R15") (pin "1") (pinfunction "1_1") (pintype "passive"))
      (node (ref "R17") (pin "1") (pinfunction "1_1") (pintype "passive"))
      (node (ref "R18") (pin "1") (pinfunction "1_1") (pintype "passive"))
      (node (ref "R22") (pin "1") (pinfunction "1_1") (pintype "passive"))
      (node (ref "RESET") (pin "3") (pinfunction "3_3") (pintype "passive"))
      (node (ref "RESET") (pin "4") (pinfunction "4_4") (pintype "passive"))
      (node (ref "UART") (pin "1") (pinfunction "1_1") (pintype "passive"))
      (node (ref "USB") (pin "GND") (pinfunction "GND_GND") (pintype "bidirectional"))
      (node (ref "VR1") (pin "2") (pinfunction "GND_2") (pintype "bidirectional"))
      (node (ref "VR2") (pin "2") (pinfunction "GND_2") (pintype "bidirectional"))
      (node (ref "VR3") (pin "2") (pinfunction "GND_2") (pintype "bidirectional"))
    )
    (net (code "51") (name "Net-(D3-PadA)") (class "Default")
      (node (ref "D3") (pin "A") (pinfunction "A_A") (pintype "passive"))
      (node (ref "JP1") (pin "1") (pinfunction "1_1") (pintype "passive"))
    )
    (net (code "52") (name "Net-(IC2A-B)") (class "Default")
      (node (ref "IC2") (pin "2") (pinfunction "B_2") (pintype "tri_state"))
      (node (ref "RN1") (pin "5") (pinfunction "2_5") (pintype "passive"))
    )
    (net (code "53") (name "Net-(IC2B-B)") (class "Default")
      (node (ref "IC2") (pin "3") (pinfunction "B_3") (pintype "tri_state"))
      (node (ref "RN1") (pin "6") (pinfunction "2_6") (pintype "passive"))
    )
    (net (code "54") (name "Net-(IC2C-B)") (class "Default")
      (node (ref "IC2") (pin "9") (pinfunction "B_9") (pintype "tri_state"))
      (node (ref "RN1") (pin "8") (pinfunction "2_8") (pintype "passive"))
    )
    (net (code "55") (name "Net-(IC2D-B)") (class "Default")
      (node (ref "IC2") (pin "11") (pinfunction "B_11") (pintype "tri_state"))
      (node (ref "RN1") (pin "7") (pinfunction "2_7") (pintype "passive"))
    )
    (net (code "56") (name "Net-(IC9-PD0{slash}5V{slash}OSC_IN)") (class "Default")
      (node (ref "C2") (pin "2") (pinfunction "2_2") (pintype "passive"))
      (node (ref "IC9") (pin "5") (pinfunction "PD0/5V/OSC_IN_5") (pintype "input"))
      (node (ref "XTAL1") (pin "2") (pinfunction "2_2") (pintype "passive"))
    )
    (net (code "57") (name "Net-(IC9-PD1{slash}5V{slash}OSC_OUT)") (class "Default")
      (node (ref "C1") (pin "2") (pinfunction "2_2") (pintype "passive"))
      (node (ref "IC9") (pin "6") (pinfunction "PD1/5V/OSC_OUT_6") (pintype "output"))
      (node (ref "XTAL1") (pin "1") (pinfunction "1_1") (pintype "passive"))
    )
    (net (code "58") (name "Net-(LED1-PadA)") (class "Default")
      (node (ref "LED1") (pin "A") (pinfunction "A_A") (pintype "passive"))
      (node (ref "LED1A") (pin "A") (pinfunction "A_A") (pintype "passive"))
      (node (ref "R3") (pin "1") (pinfunction "1_1") (pintype "passive"))
    )
    (net (code "59") (name "Net-(LED2-PadA)") (class "Default")
      (node (ref "LED2") (pin "A") (pinfunction "A_A") (pintype "passive"))
      (node (ref "LED2A") (pin "A") (pinfunction "A_A") (pintype "passive"))
      (node (ref "R5") (pin "1") (pinfunction "1_1") (pintype "passive"))
    )
    (net (code "60") (name "Net-(LED3-PadA)") (class "Default")
      (node (ref "LED3") (pin "A") (pinfunction "A_A") (pintype "passive"))
      (node (ref "LED3A") (pin "A") (pinfunction "A_A") (pintype "passive"))
      (node (ref "R6") (pin "1") (pinfunction "1_1") (pintype "passive"))
    )
    (net (code "61") (name "Net-(LED4-PadA)") (class "Default")
      (node (ref "LED4") (pin "A") (pinfunction "A_A") (pintype "passive"))
      (node (ref "LED4A") (pin "A") (pinfunction "A_A") (pintype "passive"))
      (node (ref "R4") (pin "1") (pinfunction "1_1") (pintype "passive"))
    )
    (net (code "62") (name "Net-(Q1-B)") (class "Default")
      (node (ref "Q1") (pin "1") (pinfunction "B_1") (pintype "passive"))
      (node (ref "R1") (pin "1") (pinfunction "1_1") (pintype "passive"))
      (node (ref "R13") (pin "2") (pinfunction "2_2") (pintype "passive"))
    )
    (net (code "63") (name "Net-(Q1-C)") (class "Default")
      (node (ref "D1") (pin "A") (pinfunction "A_A") (pintype "passive"))
      (node (ref "Q1") (pin "3") (pinfunction "C_3") (pintype "passive"))
    )
    (net (code "64") (name "Net-(Q2-B)") (class "Default")
      (node (ref "Q2") (pin "1") (pinfunction "B_1") (pintype "passive"))
      (node (ref "R14") (pin "2") (pinfunction "2_2") (pintype "passive"))
      (node (ref "R2") (pin "1") (pinfunction "1_1") (pintype "passive"))
    )
    (net (code "65") (name "Net-(Q2-C)") (class "Default")
      (node (ref "D2") (pin "A") (pinfunction "A_A") (pintype "passive"))
      (node (ref "Q2") (pin "3") (pinfunction "C_3") (pintype "passive"))
    )
    (net (code "66") (name "V+") (class "Default")
      (node (ref "C11") (pin "1") (pinfunction "1_1") (pintype "passive"))
      (node (ref "C12") (pin "1") (pinfunction "1_1") (pintype "passive"))
      (node (ref "C13") (pin "1") (pinfunction "1_1") (pintype "passive"))
      (node (ref "C14") (pin "2") (pinfunction "2_2") (pintype "passive"))
      (node (ref "C17") (pin "1") (pinfunction "1_1") (pintype "passive"))
      (node (ref "C19") (pin "+") (pinfunction "+_+") (pintype "passive"))
      (node (ref "C4") (pin "2") (pinfunction "2_2") (pintype "passive"))
      (node (ref "C5") (pin "2") (pinfunction "2_2") (pintype "passive"))
      (node (ref "C6") (pin "1") (pinfunction "1_1") (pintype "passive"))
      (node (ref "C7") (pin "2") (pinfunction "2_2") (pintype "passive"))
      (node (ref "C8") (pin "2") (pinfunction "2_2") (pintype "passive"))
      (node (ref "C9") (pin "2") (pinfunction "2_2") (pintype "passive"))
      (node (ref "IC3") (pin "4") (pinfunction "VCC_4") (pintype "power_in"))
      (node (ref "IC4") (pin "2") (pinfunction "SO/SIO1_2") (pintype "bidirectional"))
      (node (ref "IC4") (pin "3") (pinfunction "SIO2_3") (pintype "bidirectional"))
      (node (ref "IC4") (pin "7") (pinfunction "~{HOLD/SIO3}_7") (pintype "input"))
      (node (ref "IC4") (pin "8") (pinfunction "V+_8") (pintype "power_in"))
      (node (ref "IC5") (pin "8") (pinfunction "V+_8") (pintype "power_in"))
      (node (ref "IC6") (pin "11") (pinfunction "LE_11") (pintype "input"))
      (node (ref "IC6") (pin "20") (pinfunction "V+_20") (pintype "power_in"))
      (node (ref "IC9") (pin "1") (pinfunction "VBAT_1") (pintype "power_in"))
      (node (ref "IC9") (pin "13") (pinfunction "VDDA_13") (pintype "power_in"))
      (node (ref "IC9") (pin "19") (pinfunction "VDD_4_19") (pintype "power_in"))
      (node (ref "IC9") (pin "32") (pinfunction "VDD_1_32") (pintype "power_in"))
      (node (ref "IC9") (pin "48") (pinfunction "VDD_2_48") (pintype "power_in"))
      (node (ref "IC9") (pin "64") (pinfunction "VDD_3_64") (pintype "power_in"))
      (node (ref "JTAG") (pin "1") (pinfunction "1_1") (pintype "passive"))
      (node (ref "R20") (pin "2") (pinfunction "2_2") (pintype "passive"))
      (node (ref "R21") (pin "2") (pinfunction "2_2") (pintype "passive"))
      (node (ref "R3") (pin "2") (pinfunction "2_2") (pintype "passive"))
      (node (ref "R8") (pin "2") (pinfunction "2_2") (pintype "passive"))
      (node (ref "R9") (pin "2") (pinfunction "2_2") (pintype "passive"))
      (node (ref "VR1") (pin "5") (pinfunction "OUT_5") (pintype "bidirectional"))
    )
    (net (code "67") (name "unconnected-(IC6A-1Q-Pad19)") (class "Default")
      (node (ref "IC6") (pin "19") (pinfunction "1Q_19") (pintype "bidirectional"))
    )
    (net (code "68") (name "unconnected-(IC6A-7Q-Pad13)") (class "Default")
      (node (ref "IC6") (pin "13") (pinfunction "7Q_13") (pintype "bidirectional"))
    )
    (net (code "69") (name "unconnected-(IC6A-8Q-Pad12)") (class "Default")
      (node (ref "IC6") (pin "12") (pinfunction "8Q_12") (pintype "bidirectional"))
    )
    (net (code "70") (name "unconnected-(IC9-5V{slash}PC10-Pad51)") (class "Default")
      (node (ref "IC9") (pin "51") (pinfunction "5V/PC10_51") (pintype "bidirectional"))
    )
    (net (code "71") (name "unconnected-(IC9-5V{slash}PC11-Pad52)") (class "Default")
      (node (ref "IC9") (pin "52") (pinfunction "5V/PC11_52") (pintype "bidirectional"))
    )
    (net (code "72") (name "unconnected-(IC9-5V{slash}PC12-Pad53)") (class "Default")
      (node (ref "IC9") (pin "53") (pinfunction "5V/PC12_53") (pintype "bidirectional"))
    )
    (net (code "73") (name "unconnected-(IC9-PA10{slash}5V{slash}USART1_RX{slash}TIM1_CH3-Pad43)") (class "Default")
      (node (ref "IC9") (pin "43") (pinfunction "PA10/5V/USART1_RX/TIM1_CH3_43") (pintype "bidirectional"))
    )
    (net (code "74") (name "unconnected-(IC9-PD2{slash}5V{slash}TIM3_ETR-Pad54)") (class "Default")
      (node (ref "IC9") (pin "54") (pinfunction "PD2/5V/TIM3_ETR_54") (pintype "bidirectional"))
    )
    (net (code "75") (name "unconnected-(USBB-USBID-PadID)") (class "Default")
      (node (ref "USB") (pin "ID") (pinfunction "USBID_ID") (pintype "bidirectional"))
    )
    (net (code "76") (name "unconnected-(VR1-BYP-Pad4)") (class "Default")
      (node (ref "VR1") (pin "4") (pinfunction "BYP_4") (pintype "bidirectional"))
    )
    (net (code "77") (name "unconnected-(VR2-BYP-Pad4)") (class "Default")
      (node (ref "VR2") (pin "4") (pinfunction "BYP_4") (pintype "bidirectional"))
    )
    (net (code "78") (name "unconnected-(VR3-BYP-Pad4)") (class "Default")
      (node (ref "VR3") (pin "4") (pinfunction "BYP_4") (pintype "bidirectional"))
    )
  )
)
